# FPGA_DDR3_Interface.net
KiCad netlist of a schematic drawn in Altium Designer
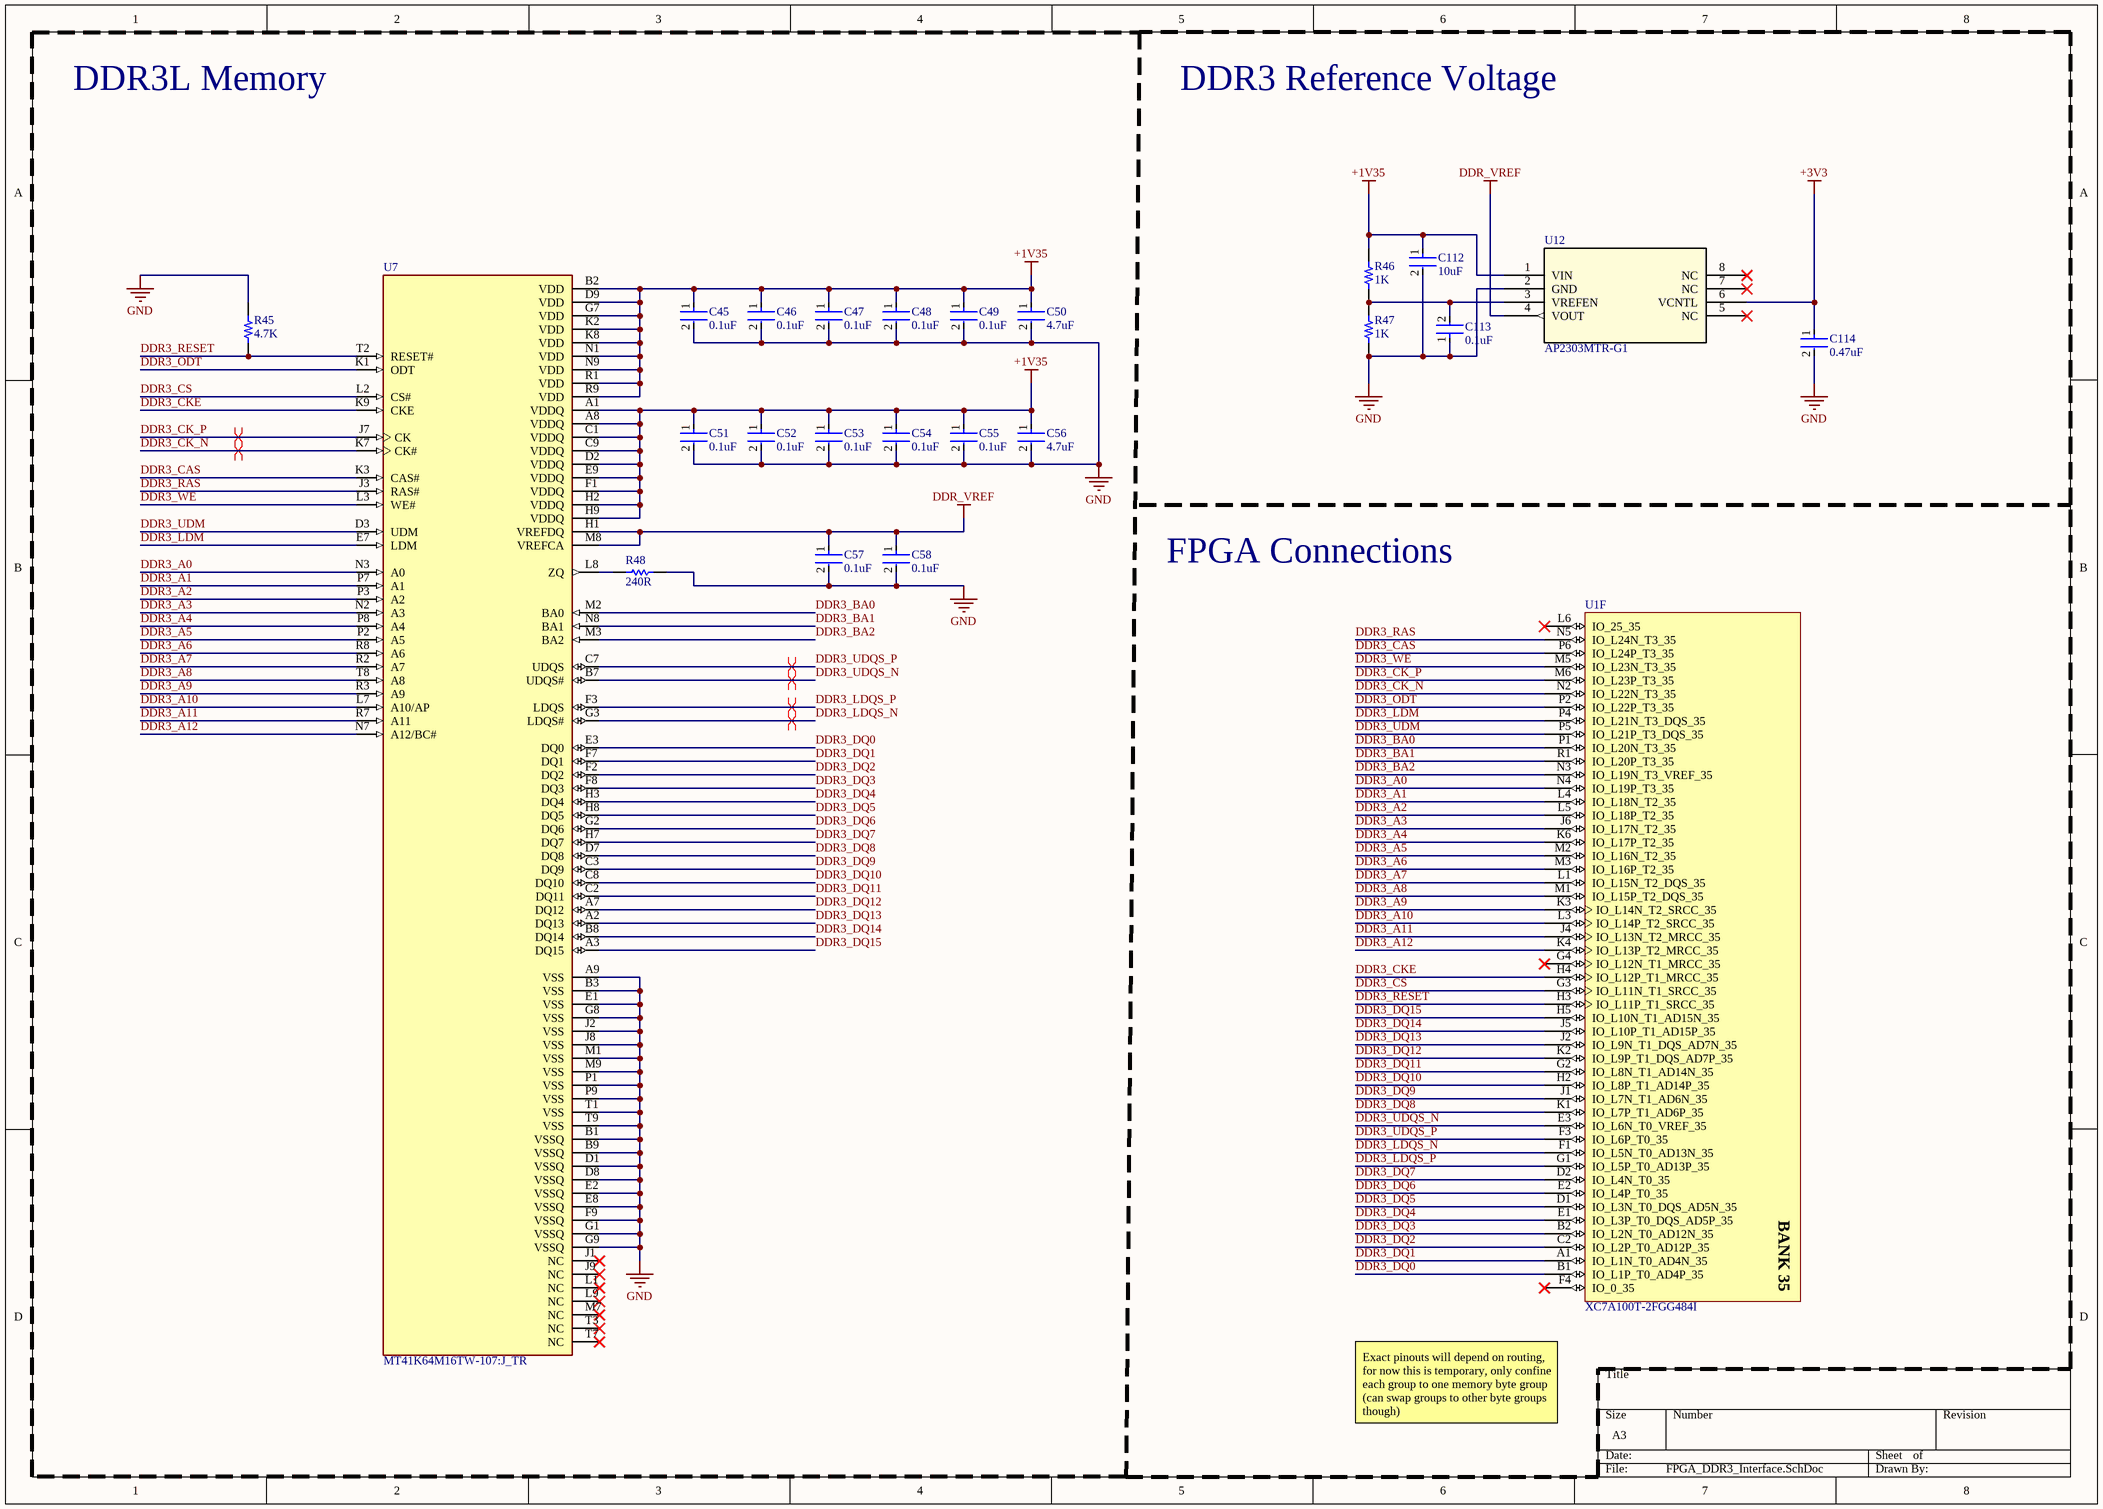
[diagram p0: FPGA_DDR3_Interface.SchDoc]

(export (version "E")
  (design (tool "Eeschema 10.0.6"))
  (components
    (comp (ref "C45")
      (value "0.1uF")
      (footprint "FP-CC0402-MFG")
      (description "CAP CER 0.1UF 16V X7R 0402")
      (fields (field (name "MANUFACTURER") "YAGEO") (field (name "TOLERANCE") "0.1"))
      (libsource (lib "Altium Content Vault") (part "11868f565c42a9108669ba33697ecf6"))
    )
    (comp (ref "C46")
      (value "0.1uF")
      (footprint "FP-CC0402-MFG")
      (description "CAP CER 0.1UF 16V X7R 0402")
      (fields (field (name "MANUFACTURER") "YAGEO") (field (name "TOLERANCE") "0.1"))
      (libsource (lib "Altium Content Vault") (part "11868f565c42a9108669ba33697ecf6"))
    )
    (comp (ref "C47")
      (value "0.1uF")
      (footprint "FP-CC0402-MFG")
      (description "CAP CER 0.1UF 16V X7R 0402")
      (fields (field (name "MANUFACTURER") "YAGEO") (field (name "TOLERANCE") "0.1"))
      (libsource (lib "Altium Content Vault") (part "11868f565c42a9108669ba33697ecf6"))
    )
    (comp (ref "C48")
      (value "0.1uF")
      (footprint "FP-CC0402-MFG")
      (description "CAP CER 0.1UF 16V X7R 0402")
      (fields (field (name "MANUFACTURER") "YAGEO") (field (name "TOLERANCE") "0.1"))
      (libsource (lib "Altium Content Vault") (part "11868f565c42a9108669ba33697ecf6"))
    )
    (comp (ref "C49")
      (value "0.1uF")
      (footprint "FP-CC0402-MFG")
      (description "CAP CER 0.1UF 16V X7R 0402")
      (fields (field (name "MANUFACTURER") "YAGEO") (field (name "TOLERANCE") "0.1"))
      (libsource (lib "Altium Content Vault") (part "11868f565c42a9108669ba33697ecf6"))
    )
    (comp (ref "C50")
      (value "4.7uF")
      (footprint "FP-CC0402-MFG")
      (description "CAP CER 4.7UF 10V X5R 0402")
      (fields
        (field (name "MANUFACTURER PART NUMBER") "CC0402MRX5R6BB475")
        (field (name "OCTOPART") "https://octopart.com/cc0402mrx5r6bb475-yageo-57080755")
      )
      (libsource (lib "Altium Content Vault") (part "11868f565c42a9108669ba33697ecf6"))
    )
    (comp (ref "C51")
      (value "0.1uF")
      (footprint "FP-CC0402-MFG")
      (description "CAP CER 0.1UF 16V X7R 0402")
      (fields (field (name "MANUFACTURER") "YAGEO") (field (name "TOLERANCE") "0.1"))
      (libsource (lib "Altium Content Vault") (part "11868f565c42a9108669ba33697ecf6"))
    )
    (comp (ref "C52")
      (value "0.1uF")
      (footprint "FP-CC0402-MFG")
      (description "CAP CER 0.1UF 16V X7R 0402")
      (fields (field (name "MANUFACTURER") "YAGEO") (field (name "TOLERANCE") "0.1"))
      (libsource (lib "Altium Content Vault") (part "11868f565c42a9108669ba33697ecf6"))
    )
    (comp (ref "C53")
      (value "0.1uF")
      (footprint "FP-CC0402-MFG")
      (description "CAP CER 0.1UF 16V X7R 0402")
      (fields (field (name "MANUFACTURER") "YAGEO") (field (name "TOLERANCE") "0.1"))
      (libsource (lib "Altium Content Vault") (part "11868f565c42a9108669ba33697ecf6"))
    )
    (comp (ref "C54")
      (value "0.1uF")
      (footprint "FP-CC0402-MFG")
      (description "CAP CER 0.1UF 16V X7R 0402")
      (fields (field (name "MANUFACTURER") "YAGEO") (field (name "TOLERANCE") "0.1"))
      (libsource (lib "Altium Content Vault") (part "11868f565c42a9108669ba33697ecf6"))
    )
    (comp (ref "C55")
      (value "0.1uF")
      (footprint "FP-CC0402-MFG")
      (description "CAP CER 0.1UF 16V X7R 0402")
      (fields (field (name "MANUFACTURER") "YAGEO") (field (name "TOLERANCE") "0.1"))
      (libsource (lib "Altium Content Vault") (part "11868f565c42a9108669ba33697ecf6"))
    )
    (comp (ref "C56")
      (value "4.7uF")
      (footprint "FP-CC0402-MFG")
      (description "CAP CER 4.7UF 10V X5R 0402")
      (fields
        (field (name "MANUFACTURER PART NUMBER") "CC0402MRX5R6BB475")
        (field (name "OCTOPART") "https://octopart.com/cc0402mrx5r6bb475-yageo-57080755")
      )
      (libsource (lib "Altium Content Vault") (part "11868f565c42a9108669ba33697ecf6"))
    )
    (comp (ref "C57")
      (value "0.1uF")
      (footprint "FP-CC0402-MFG")
      (description "CAP CER 0.1UF 16V X7R 0402")
      (fields (field (name "MANUFACTURER") "YAGEO") (field (name "TOLERANCE") "0.1"))
      (libsource (lib "Altium Content Vault") (part "11868f565c42a9108669ba33697ecf6"))
    )
    (comp (ref "C58")
      (value "0.1uF")
      (footprint "FP-CC0402-MFG")
      (description "CAP CER 0.1UF 16V X7R 0402")
      (fields (field (name "MANUFACTURER") "YAGEO") (field (name "TOLERANCE") "0.1"))
      (libsource (lib "Altium Content Vault") (part "11868f565c42a9108669ba33697ecf6"))
    )
    (comp (ref "C112")
      (value "10uF")
      (footprint "FP-GRM155-0_2-IPC_C")
      (description "Chip Multilayer Ceramic Capacitors for General Purpose, 0402, 10uF, X5R, 15%, 20%, 6.3V")
      (libsource (lib "Altium Content Vault") (part "b4654b650e69147ec39a6b967a45e02"))
    )
    (comp (ref "C113")
      (value "0.1uF")
      (footprint "FP-CC0402-MFG")
      (description "CAP CER 0.1UF 16V X7R 0402")
      (fields (field (name "MANUFACTURER") "YAGEO") (field (name "TOLERANCE") "0.1"))
      (libsource (lib "Altium Content Vault") (part "11868f565c42a9108669ba33697ecf6"))
    )
    (comp (ref "C114")
      (value "0.47uF")
      (footprint "FP-GRM188-0_1-e0_2_0_5-MFG")
      (description "Chip Multilayer Ceramic Capacitors for General Purpose, 0603, 0.47uF, X7R, 15%, 10%, 25V")
      (fields (field (name "TOLERANCE") "10%") (field (name "VOLTAGE") "50V"))
      (libsource (lib "Altium Content Vault") (part "11868f565c42a9108669ba33697ecf6"))
    )
    (comp (ref "R45")
      (value "4.7K")
      (footprint "RES 0603_1608")
      (libsource (lib "Midnight Sun") (part "Resistor"))
    )
    (comp (ref "R46")
      (value "1K")
      (footprint "RES 0603_1608")
      (description "1 kOhms ±1% 0.1W, 1/10W Chip Resistor 0603 (1608 Metric) Moisture Resistant Thick Film")
      (libsource (lib "Midnight Sun") (part "Resistor"))
    )
    (comp (ref "R47")
      (value "1K")
      (footprint "RES 0603_1608")
      (description "1 kOhms ±1% 0.1W, 1/10W Chip Resistor 0603 (1608 Metric) Moisture Resistant Thick Film")
      (libsource (lib "Midnight Sun") (part "Resistor"))
    )
    (comp (ref "R48")
      (value "240R")
      (footprint "RESC0402(1005)_L")
      (description "240R 0.063W 1% 0402 (1005 Metric)  SMD")
      (fields (field (name "POWER") "0.063 W") (field (name "TOLERANCE") "1 %"))
      (libsource (lib "Altium Content Vault") (part "RES"))
    )
    (comp (ref "U1")
      (value "XC7A100T-2FGG484I")
      (footprint "FGG484")
      (description "Artix-7 FPGA, 285 User I/Os, 4 GTP, 484-Ball BGA, Speed Grade 2, Industrial Grade, Pb-Free")
      (fields (field (name "MANUFACTURER") "Xilinx") (field (name "GENERIC PART NUMBER") "XC7A100T"))
      (libsource (lib "Altium Content Vault") (part "XNLX-XC7A100T-XNLX-FGG484"))
    )
    (comp (ref "U7")
      (value "MT41K64M16TW-107:J_TR")
      (footprint "BGA96C80P9X16_1400X800X120N")
      (description "SDRAM - DDR3L Memory IC 1Gb (64M x 16) Parallel 933MHz 20ns 96-FBGA (8x14)")
      (fields (field (name "MF") "Micron Technology Inc.") (field (name "MP") "MT41K64M16TW-107:J TR"))
      (libsource (lib "BIG_FPGA") (part "MT41K64M16TW-107{colon}J_TR"))
    )
    (comp (ref "U12")
      (value "AP2303MTR-G1")
      (footprint "SOIC-8_AP2303MTR-G1_DIO-M")
      (description "No Description Available")
      (libsource (lib "BIG_FPGA") (part "AP2303MTR-G1"))
    )
  )
  (nets
    (net (code "1") (name "+1V35") (class "Default")
      (node (ref "C112") (pin "1") (pinfunction "1_1") (pintype "passive"))
      (node (ref "C45") (pin "1") (pinfunction "1_1") (pintype "passive"))
      (node (ref "C46") (pin "1") (pinfunction "1_1") (pintype "passive"))
      (node (ref "C47") (pin "1") (pinfunction "1_1") (pintype "passive"))
      (node (ref "C48") (pin "1") (pinfunction "1_1") (pintype "passive"))
      (node (ref "C49") (pin "1") (pinfunction "1_1") (pintype "passive"))
      (node (ref "C50") (pin "1") (pinfunction "1_1") (pintype "passive"))
      (node (ref "C51") (pin "1") (pinfunction "1_1") (pintype "passive"))
      (node (ref "C52") (pin "1") (pinfunction "1_1") (pintype "passive"))
      (node (ref "C53") (pin "1") (pinfunction "1_1") (pintype "passive"))
      (node (ref "C54") (pin "1") (pinfunction "1_1") (pintype "passive"))
      (node (ref "C55") (pin "1") (pinfunction "1_1") (pintype "passive"))
      (node (ref "C56") (pin "1") (pinfunction "1_1") (pintype "passive"))
      (node (ref "R46") (pin "1") (pinfunction "1_1") (pintype "passive"))
      (node (ref "U12") (pin "1") (pinfunction "VIN_1") (pintype "passive"))
      (node (ref "U7") (pin "A1") (pinfunction "VDDQ_A1") (pintype "power_in"))
      (node (ref "U7") (pin "A8") (pinfunction "VDDQ_A8") (pintype "power_in"))
      (node (ref "U7") (pin "B2") (pinfunction "VDD_B2") (pintype "power_in"))
      (node (ref "U7") (pin "C1") (pinfunction "VDDQ_C1") (pintype "power_in"))
      (node (ref "U7") (pin "C9") (pinfunction "VDDQ_C9") (pintype "power_in"))
      (node (ref "U7") (pin "D2") (pinfunction "VDDQ_D2") (pintype "power_in"))
      (node (ref "U7") (pin "D9") (pinfunction "VDD_D9") (pintype "power_in"))
      (node (ref "U7") (pin "E9") (pinfunction "VDDQ_E9") (pintype "power_in"))
      (node (ref "U7") (pin "F1") (pinfunction "VDDQ_F1") (pintype "power_in"))
      (node (ref "U7") (pin "G7") (pinfunction "VDD_G7") (pintype "power_in"))
      (node (ref "U7") (pin "H2") (pinfunction "VDDQ_H2") (pintype "power_in"))
      (node (ref "U7") (pin "H9") (pinfunction "VDDQ_H9") (pintype "power_in"))
      (node (ref "U7") (pin "K2") (pinfunction "VDD_K2") (pintype "power_in"))
      (node (ref "U7") (pin "K8") (pinfunction "VDD_K8") (pintype "power_in"))
      (node (ref "U7") (pin "N1") (pinfunction "VDD_N1") (pintype "power_in"))
      (node (ref "U7") (pin "N9") (pinfunction "VDD_N9") (pintype "power_in"))
      (node (ref "U7") (pin "R1") (pinfunction "VDD_R1") (pintype "power_in"))
      (node (ref "U7") (pin "R9") (pinfunction "VDD_R9") (pintype "power_in"))
    )
    (net (code "2") (name "+3V3") (class "Default")
      (node (ref "C114") (pin "1") (pinfunction "1_1") (pintype "passive"))
      (node (ref "U12") (pin "6") (pinfunction "VCNTL_6") (pintype "passive"))
    )
    (net (code "3") (name "/DDR3_A0") (class "Default")
      (node (ref "U1") (pin "N4") (pinfunction "IO_L19P_T3_35_N4") (pintype "bidirectional"))
      (node (ref "U7") (pin "N3") (pinfunction "A0_N3") (pintype "input"))
    )
    (net (code "4") (name "/DDR3_A1") (class "Default")
      (node (ref "U1") (pin "L4") (pinfunction "IO_L18N_T2_35_L4") (pintype "bidirectional"))
      (node (ref "U7") (pin "P7") (pinfunction "A1_P7") (pintype "input"))
    )
    (net (code "5") (name "/DDR3_A2") (class "Default")
      (node (ref "U1") (pin "L5") (pinfunction "IO_L18P_T2_35_L5") (pintype "bidirectional"))
      (node (ref "U7") (pin "P3") (pinfunction "A2_P3") (pintype "input"))
    )
    (net (code "6") (name "/DDR3_A3") (class "Default")
      (node (ref "U1") (pin "J6") (pinfunction "IO_L17N_T2_35_J6") (pintype "bidirectional"))
      (node (ref "U7") (pin "N2") (pinfunction "A3_N2") (pintype "input"))
    )
    (net (code "7") (name "/DDR3_A4") (class "Default")
      (node (ref "U1") (pin "K6") (pinfunction "IO_L17P_T2_35_K6") (pintype "bidirectional"))
      (node (ref "U7") (pin "P8") (pinfunction "A4_P8") (pintype "input"))
    )
    (net (code "8") (name "/DDR3_A5") (class "Default")
      (node (ref "U1") (pin "M2") (pinfunction "IO_L16N_T2_35_M2") (pintype "bidirectional"))
      (node (ref "U7") (pin "P2") (pinfunction "A5_P2") (pintype "input"))
    )
    (net (code "9") (name "/DDR3_A6") (class "Default")
      (node (ref "U1") (pin "M3") (pinfunction "IO_L16P_T2_35_M3") (pintype "bidirectional"))
      (node (ref "U7") (pin "R8") (pinfunction "A6_R8") (pintype "input"))
    )
    (net (code "10") (name "/DDR3_A7") (class "Default")
      (node (ref "U1") (pin "L1") (pinfunction "IO_L15N_T2_DQS_35_L1") (pintype "bidirectional"))
      (node (ref "U7") (pin "R2") (pinfunction "A7_R2") (pintype "input"))
    )
    (net (code "11") (name "/DDR3_A8") (class "Default")
      (node (ref "U1") (pin "M1") (pinfunction "IO_L15P_T2_DQS_35_M1") (pintype "bidirectional"))
      (node (ref "U7") (pin "T8") (pinfunction "A8_T8") (pintype "input"))
    )
    (net (code "12") (name "/DDR3_A9") (class "Default")
      (node (ref "U1") (pin "K3") (pinfunction "IO_L14N_T2_SRCC_35_K3") (pintype "bidirectional"))
      (node (ref "U7") (pin "R3") (pinfunction "A9_R3") (pintype "input"))
    )
    (net (code "13") (name "/DDR3_A10") (class "Default")
      (node (ref "U1") (pin "L3") (pinfunction "IO_L14P_T2_SRCC_35_L3") (pintype "bidirectional"))
      (node (ref "U7") (pin "L7") (pinfunction "A10/AP_L7") (pintype "input"))
    )
    (net (code "14") (name "/DDR3_A11") (class "Default")
      (node (ref "U1") (pin "J4") (pinfunction "IO_L13N_T2_MRCC_35_J4") (pintype "bidirectional"))
      (node (ref "U7") (pin "R7") (pinfunction "A11_R7") (pintype "input"))
    )
    (net (code "15") (name "/DDR3_A12") (class "Default")
      (node (ref "U1") (pin "K4") (pinfunction "IO_L13P_T2_MRCC_35_K4") (pintype "bidirectional"))
      (node (ref "U7") (pin "N7") (pinfunction "A12/BC#_N7") (pintype "input"))
    )
    (net (code "16") (name "/DDR3_BA0") (class "Default")
      (node (ref "U1") (pin "P1") (pinfunction "IO_L20N_T3_35_P1") (pintype "bidirectional"))
      (node (ref "U7") (pin "M2") (pinfunction "BA0_M2") (pintype "input"))
    )
    (net (code "17") (name "/DDR3_BA1") (class "Default")
      (node (ref "U1") (pin "R1") (pinfunction "IO_L20P_T3_35_R1") (pintype "bidirectional"))
      (node (ref "U7") (pin "N8") (pinfunction "BA1_N8") (pintype "input"))
    )
    (net (code "18") (name "/DDR3_BA2") (class "Default")
      (node (ref "U1") (pin "N3") (pinfunction "IO_L19N_T3_VREF_35_N3") (pintype "bidirectional"))
      (node (ref "U7") (pin "M3") (pinfunction "BA2_M3") (pintype "input"))
    )
    (net (code "19") (name "/DDR3_CAS") (class "Default")
      (node (ref "U1") (pin "P6") (pinfunction "IO_L24P_T3_35_P6") (pintype "bidirectional"))
      (node (ref "U7") (pin "K3") (pinfunction "CAS#_K3") (pintype "input"))
    )
    (net (code "20") (name "/DDR3_CKE") (class "Default")
      (node (ref "U1") (pin "H4") (pinfunction "IO_L12P_T1_MRCC_35_H4") (pintype "bidirectional"))
      (node (ref "U7") (pin "K9") (pinfunction "CKE_K9") (pintype "input"))
    )
    (net (code "21") (name "/DDR3_CK_N") (class "Default")
      (node (ref "U1") (pin "N2") (pinfunction "IO_L22N_T3_35_N2") (pintype "bidirectional"))
      (node (ref "U7") (pin "K7") (pinfunction "CK#_K7") (pintype "input"))
    )
    (net (code "22") (name "/DDR3_CK_P") (class "Default")
      (node (ref "U1") (pin "M6") (pinfunction "IO_L23P_T3_35_M6") (pintype "bidirectional"))
      (node (ref "U7") (pin "J7") (pinfunction "CK_J7") (pintype "input"))
    )
    (net (code "23") (name "/DDR3_CS") (class "Default")
      (node (ref "U1") (pin "G3") (pinfunction "IO_L11N_T1_SRCC_35_G3") (pintype "bidirectional"))
      (node (ref "U7") (pin "L2") (pinfunction "CS#_L2") (pintype "input"))
    )
    (net (code "24") (name "/DDR3_DQ0") (class "Default")
      (node (ref "U1") (pin "B1") (pinfunction "IO_L1P_T0_AD4P_35_B1") (pintype "bidirectional"))
      (node (ref "U7") (pin "E3") (pinfunction "DQ0_E3") (pintype "bidirectional"))
    )
    (net (code "25") (name "/DDR3_DQ1") (class "Default")
      (node (ref "U1") (pin "A1") (pinfunction "IO_L1N_T0_AD4N_35_A1") (pintype "bidirectional"))
      (node (ref "U7") (pin "F7") (pinfunction "DQ1_F7") (pintype "bidirectional"))
    )
    (net (code "26") (name "/DDR3_DQ2") (class "Default")
      (node (ref "U1") (pin "C2") (pinfunction "IO_L2P_T0_AD12P_35_C2") (pintype "bidirectional"))
      (node (ref "U7") (pin "F2") (pinfunction "DQ2_F2") (pintype "bidirectional"))
    )
    (net (code "27") (name "/DDR3_DQ3") (class "Default")
      (node (ref "U1") (pin "B2") (pinfunction "IO_L2N_T0_AD12N_35_B2") (pintype "bidirectional"))
      (node (ref "U7") (pin "F8") (pinfunction "DQ3_F8") (pintype "bidirectional"))
    )
    (net (code "28") (name "/DDR3_DQ4") (class "Default")
      (node (ref "U1") (pin "E1") (pinfunction "IO_L3P_T0_DQS_AD5P_35_E1") (pintype "bidirectional"))
      (node (ref "U7") (pin "H3") (pinfunction "DQ4_H3") (pintype "bidirectional"))
    )
    (net (code "29") (name "/DDR3_DQ5") (class "Default")
      (node (ref "U1") (pin "D1") (pinfunction "IO_L3N_T0_DQS_AD5N_35_D1") (pintype "bidirectional"))
      (node (ref "U7") (pin "H8") (pinfunction "DQ5_H8") (pintype "bidirectional"))
    )
    (net (code "30") (name "/DDR3_DQ6") (class "Default")
      (node (ref "U1") (pin "E2") (pinfunction "IO_L4P_T0_35_E2") (pintype "bidirectional"))
      (node (ref "U7") (pin "G2") (pinfunction "DQ6_G2") (pintype "bidirectional"))
    )
    (net (code "31") (name "/DDR3_DQ7") (class "Default")
      (node (ref "U1") (pin "D2") (pinfunction "IO_L4N_T0_35_D2") (pintype "bidirectional"))
      (node (ref "U7") (pin "H7") (pinfunction "DQ7_H7") (pintype "bidirectional"))
    )
    (net (code "32") (name "/DDR3_DQ8") (class "Default")
      (node (ref "U1") (pin "K1") (pinfunction "IO_L7P_T1_AD6P_35_K1") (pintype "bidirectional"))
      (node (ref "U7") (pin "D7") (pinfunction "DQ8_D7") (pintype "bidirectional"))
    )
    (net (code "33") (name "/DDR3_DQ9") (class "Default")
      (node (ref "U1") (pin "J1") (pinfunction "IO_L7N_T1_AD6N_35_J1") (pintype "bidirectional"))
      (node (ref "U7") (pin "C3") (pinfunction "DQ9_C3") (pintype "bidirectional"))
    )
    (net (code "34") (name "/DDR3_DQ10") (class "Default")
      (node (ref "U1") (pin "H2") (pinfunction "IO_L8P_T1_AD14P_35_H2") (pintype "bidirectional"))
      (node (ref "U7") (pin "C8") (pinfunction "DQ10_C8") (pintype "bidirectional"))
    )
    (net (code "35") (name "/DDR3_DQ11") (class "Default")
      (node (ref "U1") (pin "G2") (pinfunction "IO_L8N_T1_AD14N_35_G2") (pintype "bidirectional"))
      (node (ref "U7") (pin "C2") (pinfunction "DQ11_C2") (pintype "bidirectional"))
    )
    (net (code "36") (name "/DDR3_DQ12") (class "Default")
      (node (ref "U1") (pin "K2") (pinfunction "IO_L9P_T1_DQS_AD7P_35_K2") (pintype "bidirectional"))
      (node (ref "U7") (pin "A7") (pinfunction "DQ12_A7") (pintype "bidirectional"))
    )
    (net (code "37") (name "/DDR3_DQ13") (class "Default")
      (node (ref "U1") (pin "J2") (pinfunction "IO_L9N_T1_DQS_AD7N_35_J2") (pintype "bidirectional"))
      (node (ref "U7") (pin "A2") (pinfunction "DQ13_A2") (pintype "bidirectional"))
    )
    (net (code "38") (name "/DDR3_DQ14") (class "Default")
      (node (ref "U1") (pin "J5") (pinfunction "IO_L10P_T1_AD15P_35_J5") (pintype "bidirectional"))
      (node (ref "U7") (pin "B8") (pinfunction "DQ14_B8") (pintype "bidirectional"))
    )
    (net (code "39") (name "/DDR3_DQ15") (class "Default")
      (node (ref "U1") (pin "H5") (pinfunction "IO_L10N_T1_AD15N_35_H5") (pintype "bidirectional"))
      (node (ref "U7") (pin "A3") (pinfunction "DQ15_A3") (pintype "bidirectional"))
    )
    (net (code "40") (name "/DDR3_LDM") (class "Default")
      (node (ref "U1") (pin "P4") (pinfunction "IO_L21N_T3_DQS_35_P4") (pintype "bidirectional"))
      (node (ref "U7") (pin "E7") (pinfunction "LDM_E7") (pintype "input"))
    )
    (net (code "41") (name "/DDR3_LDQS_N") (class "Default")
      (node (ref "U1") (pin "F1") (pinfunction "IO_L5N_T0_AD13N_35_F1") (pintype "bidirectional"))
      (node (ref "U7") (pin "G3") (pinfunction "LDQS#_G3") (pintype "bidirectional"))
    )
    (net (code "42") (name "/DDR3_LDQS_P") (class "Default")
      (node (ref "U1") (pin "G1") (pinfunction "IO_L5P_T0_AD13P_35_G1") (pintype "bidirectional"))
      (node (ref "U7") (pin "F3") (pinfunction "LDQS_F3") (pintype "bidirectional"))
    )
    (net (code "43") (name "/DDR3_ODT") (class "Default")
      (node (ref "U1") (pin "P2") (pinfunction "IO_L22P_T3_35_P2") (pintype "bidirectional"))
      (node (ref "U7") (pin "K1") (pinfunction "ODT_K1") (pintype "input"))
    )
    (net (code "44") (name "/DDR3_RAS") (class "Default")
      (node (ref "U1") (pin "N5") (pinfunction "IO_L24N_T3_35_N5") (pintype "bidirectional"))
      (node (ref "U7") (pin "J3") (pinfunction "RAS#_J3") (pintype "input"))
    )
    (net (code "45") (name "/DDR3_RESET") (class "Default")
      (node (ref "R45") (pin "1") (pinfunction "1_1") (pintype "passive"))
      (node (ref "U1") (pin "H3") (pinfunction "IO_L11P_T1_SRCC_35_H3") (pintype "bidirectional"))
      (node (ref "U7") (pin "T2") (pinfunction "RESET#_T2") (pintype "input"))
    )
    (net (code "46") (name "/DDR3_UDM") (class "Default")
      (node (ref "U1") (pin "P5") (pinfunction "IO_L21P_T3_DQS_35_P5") (pintype "bidirectional"))
      (node (ref "U7") (pin "D3") (pinfunction "UDM_D3") (pintype "input"))
    )
    (net (code "47") (name "/DDR3_UDQS_N") (class "Default")
      (node (ref "U1") (pin "E3") (pinfunction "IO_L6N_T0_VREF_35_E3") (pintype "bidirectional"))
      (node (ref "U7") (pin "B7") (pinfunction "UDQS#_B7") (pintype "bidirectional"))
    )
    (net (code "48") (name "/DDR3_UDQS_P") (class "Default")
      (node (ref "U1") (pin "F3") (pinfunction "IO_L6P_T0_35_F3") (pintype "bidirectional"))
      (node (ref "U7") (pin "C7") (pinfunction "UDQS_C7") (pintype "bidirectional"))
    )
    (net (code "49") (name "/DDR3_WE") (class "Default")
      (node (ref "U1") (pin "M5") (pinfunction "IO_L23N_T3_35_M5") (pintype "bidirectional"))
      (node (ref "U7") (pin "L3") (pinfunction "WE#_L3") (pintype "input"))
    )
    (net (code "50") (name "DDR_VREF") (class "Default")
      (node (ref "C57") (pin "1") (pinfunction "1_1") (pintype "passive"))
      (node (ref "C58") (pin "1") (pinfunction "1_1") (pintype "passive"))
      (node (ref "U12") (pin "4") (pinfunction "VOUT_4") (pintype "output"))
      (node (ref "U7") (pin "H1") (pinfunction "VREFDQ_H1") (pintype "power_in"))
      (node (ref "U7") (pin "M8") (pinfunction "VREFCA_M8") (pintype "power_in"))
    )
    (net (code "51") (name "GND") (class "Default")
      (node (ref "C112") (pin "2") (pinfunction "2_2") (pintype "passive"))
      (node (ref "C113") (pin "1") (pinfunction "1_1") (pintype "passive"))
      (node (ref "C114") (pin "2") (pinfunction "2_2") (pintype "passive"))
      (node (ref "C45") (pin "2") (pinfunction "2_2") (pintype "passive"))
      (node (ref "C46") (pin "2") (pinfunction "2_2") (pintype "passive"))
      (node (ref "C47") (pin "2") (pinfunction "2_2") (pintype "passive"))
      (node (ref "C48") (pin "2") (pinfunction "2_2") (pintype "passive"))
      (node (ref "C49") (pin "2") (pinfunction "2_2") (pintype "passive"))
      (node (ref "C50") (pin "2") (pinfunction "2_2") (pintype "passive"))
      (node (ref "C51") (pin "2") (pinfunction "2_2") (pintype "passive"))
      (node (ref "C52") (pin "2") (pinfunction "2_2") (pintype "passive"))
      (node (ref "C53") (pin "2") (pinfunction "2_2") (pintype "passive"))
      (node (ref "C54") (pin "2") (pinfunction "2_2") (pintype "passive"))
      (node (ref "C55") (pin "2") (pinfunction "2_2") (pintype "passive"))
      (node (ref "C56") (pin "2") (pinfunction "2_2") (pintype "passive"))
      (node (ref "C57") (pin "2") (pinfunction "2_2") (pintype "passive"))
      (node (ref "C58") (pin "2") (pinfunction "2_2") (pintype "passive"))
      (node (ref "R45") (pin "2") (pinfunction "2_2") (pintype "passive"))
      (node (ref "R47") (pin "2") (pinfunction "2_2") (pintype "passive"))
      (node (ref "R48") (pin "1") (pinfunction "1_1") (pintype "passive"))
      (node (ref "U12") (pin "2") (pinfunction "GND_2") (pintype "power_in"))
      (node (ref "U7") (pin "A9") (pinfunction "VSS_A9") (pintype "power_in"))
      (node (ref "U7") (pin "B1") (pinfunction "VSSQ_B1") (pintype "power_in"))
      (node (ref "U7") (pin "B3") (pinfunction "VSS_B3") (pintype "power_in"))
      (node (ref "U7") (pin "B9") (pinfunction "VSSQ_B9") (pintype "power_in"))
      (node (ref "U7") (pin "D1") (pinfunction "VSSQ_D1") (pintype "power_in"))
      (node (ref "U7") (pin "D8") (pinfunction "VSSQ_D8") (pintype "power_in"))
      (node (ref "U7") (pin "E1") (pinfunction "VSS_E1") (pintype "power_in"))
      (node (ref "U7") (pin "E2") (pinfunction "VSSQ_E2") (pintype "power_in"))
      (node (ref "U7") (pin "E8") (pinfunction "VSSQ_E8") (pintype "power_in"))
      (node (ref "U7") (pin "F9") (pinfunction "VSSQ_F9") (pintype "power_in"))
      (node (ref "U7") (pin "G1") (pinfunction "VSSQ_G1") (pintype "power_in"))
      (node (ref "U7") (pin "G8") (pinfunction "VSS_G8") (pintype "power_in"))
      (node (ref "U7") (pin "G9") (pinfunction "VSSQ_G9") (pintype "power_in"))
      (node (ref "U7") (pin "J2") (pinfunction "VSS_J2") (pintype "power_in"))
      (node (ref "U7") (pin "J8") (pinfunction "VSS_J8") (pintype "power_in"))
      (node (ref "U7") (pin "M1") (pinfunction "VSS_M1") (pintype "power_in"))
      (node (ref "U7") (pin "M9") (pinfunction "VSS_M9") (pintype "power_in"))
      (node (ref "U7") (pin "P1") (pinfunction "VSS_P1") (pintype "power_in"))
      (node (ref "U7") (pin "P9") (pinfunction "VSS_P9") (pintype "power_in"))
      (node (ref "U7") (pin "T1") (pinfunction "VSS_T1") (pintype "power_in"))
      (node (ref "U7") (pin "T9") (pinfunction "VSS_T9") (pintype "power_in"))
    )
    (net (code "52") (name "Net-(U7-ZQ)") (class "Default")
      (node (ref "R48") (pin "2") (pinfunction "2_2") (pintype "passive"))
      (node (ref "U7") (pin "L8") (pinfunction "ZQ_L8") (pintype "output"))
    )
    (net (code "53") (name "Net-(U12-VREFEN)") (class "Default")
      (node (ref "C113") (pin "2") (pinfunction "2_2") (pintype "passive"))
      (node (ref "R46") (pin "2") (pinfunction "2_2") (pintype "passive"))
      (node (ref "R47") (pin "1") (pinfunction "1_1") (pintype "passive"))
      (node (ref "U12") (pin "3") (pinfunction "VREFEN_3") (pintype "power_in"))
    )
    (net (code "54") (name "unconnected-(U1F-IO_0_35-PadF4)") (class "Default")
      (node (ref "U1") (pin "F4") (pinfunction "IO_0_35_F4") (pintype "bidirectional+no_connect"))
    )
    (net (code "55") (name "unconnected-(U1F-IO_25_35-PadL6)") (class "Default")
      (node (ref "U1") (pin "L6") (pinfunction "IO_25_35_L6") (pintype "bidirectional+no_connect"))
    )
    (net (code "56") (name "unconnected-(U1F-IO_L12N_T1_MRCC_35-PadG4)") (class "Default")
      (node (ref "U1") (pin "G4") (pinfunction "IO_L12N_T1_MRCC_35_G4") (pintype "bidirectional+no_connect"))
    )
    (net (code "57") (name "unconnected-(U7-NC-PadJ1)") (class "Default")
      (node (ref "U7") (pin "J1") (pinfunction "NC_J1") (pintype "passive+no_connect"))
    )
    (net (code "58") (name "unconnected-(U7-NC-PadJ9)") (class "Default")
      (node (ref "U7") (pin "J9") (pinfunction "NC_J9") (pintype "passive+no_connect"))
    )
    (net (code "59") (name "unconnected-(U7-NC-PadL1)") (class "Default")
      (node (ref "U7") (pin "L1") (pinfunction "NC_L1") (pintype "passive+no_connect"))
    )
    (net (code "60") (name "unconnected-(U7-NC-PadL9)") (class "Default")
      (node (ref "U7") (pin "L9") (pinfunction "NC_L9") (pintype "passive+no_connect"))
    )
    (net (code "61") (name "unconnected-(U7-NC-PadM7)") (class "Default")
      (node (ref "U7") (pin "M7") (pinfunction "NC_M7") (pintype "passive+no_connect"))
    )
    (net (code "62") (name "unconnected-(U7-NC-PadT3)") (class "Default")
      (node (ref "U7") (pin "T3") (pinfunction "NC_T3") (pintype "passive+no_connect"))
    )
    (net (code "63") (name "unconnected-(U7-NC-PadT7)") (class "Default")
      (node (ref "U7") (pin "T7") (pinfunction "NC_T7") (pintype "passive+no_connect"))
    )
    (net (code "64") (name "unconnected-(U12-NC-Pad5)") (class "Default")
      (node (ref "U12") (pin "5") (pinfunction "NC_5") (pintype "passive+no_connect"))
    )
    (net (code "65") (name "unconnected-(U12-NC-Pad7)") (class "Default")
      (node (ref "U12") (pin "7") (pinfunction "NC_7") (pintype "passive+no_connect"))
    )
    (net (code "66") (name "unconnected-(U12-NC-Pad8)") (class "Default")
      (node (ref "U12") (pin "8") (pinfunction "NC_8") (pintype "passive+no_connect"))
    )
  )
)
